# processor.net
KiCad netlist of a schematic drawn in Altium Designer
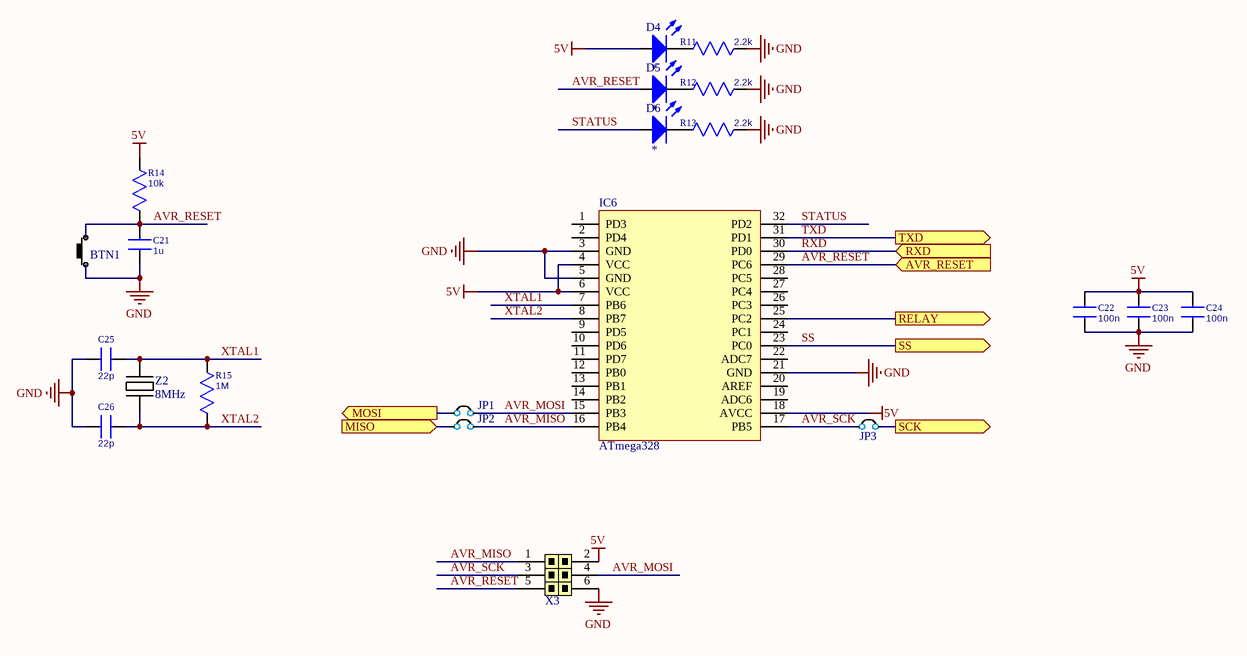
[diagram p0: processor.SchDoc]

(export (version "E")
  (design (tool "Eeschema 10.0.6"))
  (components
    (comp (ref "BTN1")
      (value "Push Button")
      (footprint "PUSH BUTTON RIGHT ANGLE")
      (description "Push button")
      (libsource (lib "TomatoBoardPCB_Project") (part "Push Button"))
    )
    (comp (ref "C21")
      (value "1u")
      (footprint "C_0603")
      (description "Capacitor")
      (libsource (lib "AX_Altium_v2.3") (part "C0603"))
    )
    (comp (ref "C22")
      (value "100n")
      (footprint "C_0603")
      (description "Capacitor")
      (libsource (lib "AX_Altium_v2.3") (part "C0603"))
    )
    (comp (ref "C23")
      (value "100n")
      (footprint "C_0603")
      (description "Capacitor")
      (libsource (lib "AX_Altium_v2.3") (part "C0603"))
    )
    (comp (ref "C24")
      (value "100n")
      (footprint "C_0603")
      (description "Capacitor")
      (libsource (lib "AX_Altium_v2.3") (part "C0603"))
    )
    (comp (ref "C25")
      (value "22p")
      (footprint "C_0603")
      (description "Capacitor")
      (libsource (lib "AX_Altium_v2.3") (part "C0603"))
    )
    (comp (ref "C26")
      (value "22p")
      (footprint "C_0603")
      (description "Capacitor")
      (libsource (lib "AX_Altium_v2.3") (part "C0603"))
    )
    (comp (ref "D4")
      (value "*")
      (footprint "LED_5mm")
      (description "Typical INFRARED GaAs LED")
      (libsource (lib "AX_Altium_v2.3") (part "LED_5mm"))
    )
    (comp (ref "D5")
      (value "*")
      (footprint "LED_5mm")
      (description "Typical INFRARED GaAs LED")
      (libsource (lib "AX_Altium_v2.3") (part "LED_5mm"))
    )
    (comp (ref "D6")
      (value "*")
      (footprint "LED_5mm")
      (description "Typical INFRARED GaAs LED")
      (libsource (lib "AX_Altium_v2.3") (part "LED_5mm"))
    )
    (comp (ref "IC6")
      (value "ATmega328")
      (footprint "TQFP-32")
      (description "High Performance, Low Power Atmel AVR 8-Bit Microcontroller")
      (libsource (lib "SmartOutletIntegratedLibrary") (part "ATmega328"))
    )
    (comp (ref "JP1")
      (value "PLS-2")
      (footprint "PLS-2")
      (description "Jumper Pins")
      (libsource (lib "Generator_Integrated_Library") (part "JP-2"))
    )
    (comp (ref "JP2")
      (value "PLS-2")
      (footprint "PLS-2")
      (description "Jumper Pins")
      (libsource (lib "Generator_Integrated_Library") (part "JP-2"))
    )
    (comp (ref "JP3")
      (value "PLS-2")
      (footprint "PLS-2")
      (description "Jumper Pins")
      (libsource (lib "Generator_Integrated_Library") (part "JP-2"))
    )
    (comp (ref "R11")
      (value "2.2k")
      (footprint "R_0603")
      (description "Resistor")
      (libsource (lib "AX_Altium_v2.3") (part "R0603"))
    )
    (comp (ref "R12")
      (value "2.2k")
      (footprint "R_0603")
      (description "Resistor")
      (libsource (lib "AX_Altium_v2.3") (part "R0603"))
    )
    (comp (ref "R13")
      (value "2.2k")
      (footprint "R_0603")
      (description "Resistor")
      (libsource (lib "AX_Altium_v2.3") (part "R0603"))
    )
    (comp (ref "R14")
      (value "10k")
      (footprint "R_0603")
      (description "Resistor")
      (libsource (lib "AX_Altium_v2.3") (part "R0603"))
    )
    (comp (ref "R15")
      (value "1M")
      (footprint "R_0603")
      (description "Resistor")
      (libsource (lib "AX_Altium_v2.3") (part "R0603"))
    )
    (comp (ref "X3")
      (value "PLD-6")
      (footprint "PLD-6")
      (libsource (lib "Light_Music_Integrated_Library") (part "PLD-6"))
    )
    (comp (ref "Z2")
      (value "8MHz")
      (footprint "HC-49")
      (description "Quartz resonator")
      (libsource (lib "Light_Music_Integrated_Library") (part "XTAL"))
    )
  )
  (nets
    (net (code "1") (name "/AVR_MISO") (class "Default")
      (node (ref "IC6") (pin "16") (pinfunction "PB4_16") (pintype "passive"))
      (node (ref "JP2") (pin "2") (pinfunction "2_2") (pintype "passive"))
      (node (ref "X3") (pin "1") (pinfunction "1_1") (pintype "passive"))
    )
    (net (code "2") (name "/AVR_MOSI") (class "Default")
      (node (ref "IC6") (pin "15") (pinfunction "PB3_15") (pintype "passive"))
      (node (ref "JP1") (pin "2") (pinfunction "2_2") (pintype "passive"))
      (node (ref "X3") (pin "4") (pinfunction "4_4") (pintype "passive"))
    )
    (net (code "3") (name "/AVR_RESET") (class "Default")
      (node (ref "BTN1") (pin "1") (pinfunction "1_1") (pintype "passive"))
      (node (ref "C21") (pin "2") (pintype "passive"))
      (node (ref "D5") (pin "1") (pinfunction "A_1") (pintype "passive"))
      (node (ref "IC6") (pin "29") (pinfunction "PC6_29") (pintype "passive"))
      (node (ref "R14") (pin "2") (pintype "passive"))
      (node (ref "X3") (pin "5") (pinfunction "5_5") (pintype "passive"))
    )
    (net (code "4") (name "/AVR_SCK") (class "Default")
      (node (ref "IC6") (pin "17") (pinfunction "PB5_17") (pintype "passive"))
      (node (ref "JP3") (pin "1") (pinfunction "1_1") (pintype "passive"))
      (node (ref "X3") (pin "3") (pinfunction "3_3") (pintype "passive"))
    )
    (net (code "5") (name "/MISO") (class "Default")
      (node (ref "JP2") (pin "1") (pinfunction "1_1") (pintype "passive"))
    )
    (net (code "6") (name "/MOSI") (class "Default")
      (node (ref "JP1") (pin "1") (pinfunction "1_1") (pintype "passive"))
    )
    (net (code "7") (name "/RELAY") (class "Default")
      (node (ref "IC6") (pin "25") (pinfunction "PC2_25") (pintype "passive"))
    )
    (net (code "8") (name "/RXD") (class "Default")
      (node (ref "IC6") (pin "30") (pinfunction "PD0_30") (pintype "passive"))
    )
    (net (code "9") (name "/SCK") (class "Default")
      (node (ref "JP3") (pin "2") (pinfunction "2_2") (pintype "passive"))
    )
    (net (code "10") (name "/SS") (class "Default")
      (node (ref "IC6") (pin "23") (pinfunction "PC0_23") (pintype "passive"))
    )
    (net (code "11") (name "/STATUS") (class "Default")
      (node (ref "D6") (pin "1") (pinfunction "A_1") (pintype "passive"))
      (node (ref "IC6") (pin "32") (pinfunction "PD2_32") (pintype "passive"))
    )
    (net (code "12") (name "/TXD") (class "Default")
      (node (ref "IC6") (pin "31") (pinfunction "PD1_31") (pintype "passive"))
    )
    (net (code "13") (name "/XTAL1") (class "Default")
      (node (ref "C25") (pin "1") (pintype "passive"))
      (node (ref "IC6") (pin "7") (pinfunction "PB6_7") (pintype "passive"))
      (node (ref "R15") (pin "1") (pintype "passive"))
      (node (ref "Z2") (pin "2") (pinfunction "2_2") (pintype "passive"))
    )
    (net (code "14") (name "/XTAL2") (class "Default")
      (node (ref "C26") (pin "1") (pintype "passive"))
      (node (ref "IC6") (pin "8") (pinfunction "PB7_8") (pintype "passive"))
      (node (ref "R15") (pin "2") (pintype "passive"))
      (node (ref "Z2") (pin "1") (pinfunction "1_1") (pintype "passive"))
    )
    (net (code "15") (name "5V") (class "Default")
      (node (ref "C22") (pin "2") (pintype "passive"))
      (node (ref "C23") (pin "2") (pintype "passive"))
      (node (ref "C24") (pin "2") (pintype "passive"))
      (node (ref "D4") (pin "1") (pinfunction "A_1") (pintype "passive"))
      (node (ref "IC6") (pin "18") (pinfunction "AVCC_18") (pintype "passive"))
      (node (ref "IC6") (pin "4") (pinfunction "VCC_4") (pintype "passive"))
      (node (ref "IC6") (pin "6") (pinfunction "VCC_6") (pintype "passive"))
      (node (ref "R14") (pin "1") (pintype "passive"))
      (node (ref "X3") (pin "2") (pinfunction "2_2") (pintype "passive"))
    )
    (net (code "16") (name "GND") (class "Default")
      (node (ref "BTN1") (pin "2") (pinfunction "2_2") (pintype "passive"))
      (node (ref "C21") (pin "1") (pintype "passive"))
      (node (ref "C22") (pin "1") (pintype "passive"))
      (node (ref "C23") (pin "1") (pintype "passive"))
      (node (ref "C24") (pin "1") (pintype "passive"))
      (node (ref "C25") (pin "2") (pintype "passive"))
      (node (ref "C26") (pin "2") (pintype "passive"))
      (node (ref "IC6") (pin "21") (pinfunction "GND_21") (pintype "passive"))
      (node (ref "IC6") (pin "3") (pinfunction "GND_3") (pintype "passive"))
      (node (ref "IC6") (pin "5") (pinfunction "GND_5") (pintype "passive"))
      (node (ref "R11") (pin "2") (pintype "passive"))
      (node (ref "R12") (pin "2") (pintype "passive"))
      (node (ref "R13") (pin "2") (pintype "passive"))
      (node (ref "X3") (pin "6") (pinfunction "6_6") (pintype "passive"))
    )
    (net (code "17") (name "Net-(D4-K)") (class "Default")
      (node (ref "D4") (pin "2") (pinfunction "K_2") (pintype "passive"))
      (node (ref "R11") (pin "1") (pintype "passive"))
    )
    (net (code "18") (name "Net-(D5-K)") (class "Default")
      (node (ref "D5") (pin "2") (pinfunction "K_2") (pintype "passive"))
      (node (ref "R12") (pin "1") (pintype "passive"))
    )
    (net (code "19") (name "Net-(D6-K)") (class "Default")
      (node (ref "D6") (pin "2") (pinfunction "K_2") (pintype "passive"))
      (node (ref "R13") (pin "1") (pintype "passive"))
    )
    (net (code "20") (name "unconnected-(IC6-ADC6-Pad19)") (class "Default")
      (node (ref "IC6") (pin "19") (pinfunction "ADC6_19") (pintype "passive"))
    )
    (net (code "21") (name "unconnected-(IC6-ADC7-Pad22)") (class "Default")
      (node (ref "IC6") (pin "22") (pinfunction "ADC7_22") (pintype "passive"))
    )
    (net (code "22") (name "unconnected-(IC6-AREF-Pad20)") (class "Default")
      (node (ref "IC6") (pin "20") (pinfunction "AREF_20") (pintype "passive"))
    )
    (net (code "23") (name "unconnected-(IC6-PB0-Pad12)") (class "Default")
      (node (ref "IC6") (pin "12") (pinfunction "PB0_12") (pintype "passive"))
    )
    (net (code "24") (name "unconnected-(IC6-PB1-Pad13)") (class "Default")
      (node (ref "IC6") (pin "13") (pinfunction "PB1_13") (pintype "passive"))
    )
    (net (code "25") (name "unconnected-(IC6-PB2-Pad14)") (class "Default")
      (node (ref "IC6") (pin "14") (pinfunction "PB2_14") (pintype "passive"))
    )
    (net (code "26") (name "unconnected-(IC6-PC1-Pad24)") (class "Default")
      (node (ref "IC6") (pin "24") (pinfunction "PC1_24") (pintype "passive"))
    )
    (net (code "27") (name "unconnected-(IC6-PC3-Pad26)") (class "Default")
      (node (ref "IC6") (pin "26") (pinfunction "PC3_26") (pintype "passive"))
    )
    (net (code "28") (name "unconnected-(IC6-PC4-Pad27)") (class "Default")
      (node (ref "IC6") (pin "27") (pinfunction "PC4_27") (pintype "passive"))
    )
    (net (code "29") (name "unconnected-(IC6-PC5-Pad28)") (class "Default")
      (node (ref "IC6") (pin "28") (pinfunction "PC5_28") (pintype "passive"))
    )
    (net (code "30") (name "unconnected-(IC6-PD3-Pad1)") (class "Default")
      (node (ref "IC6") (pin "1") (pinfunction "PD3_1") (pintype "passive"))
    )
    (net (code "31") (name "unconnected-(IC6-PD4-Pad2)") (class "Default")
      (node (ref "IC6") (pin "2") (pinfunction "PD4_2") (pintype "passive"))
    )
    (net (code "32") (name "unconnected-(IC6-PD5-Pad9)") (class "Default")
      (node (ref "IC6") (pin "9") (pinfunction "PD5_9") (pintype "passive"))
    )
    (net (code "33") (name "unconnected-(IC6-PD6-Pad10)") (class "Default")
      (node (ref "IC6") (pin "10") (pinfunction "PD6_10") (pintype "passive"))
    )
    (net (code "34") (name "unconnected-(IC6-PD7-Pad11)") (class "Default")
      (node (ref "IC6") (pin "11") (pinfunction "PD7_11") (pintype "passive"))
    )
  )
)
